# switches.net
KiCad netlist of a schematic drawn in Altium Designer
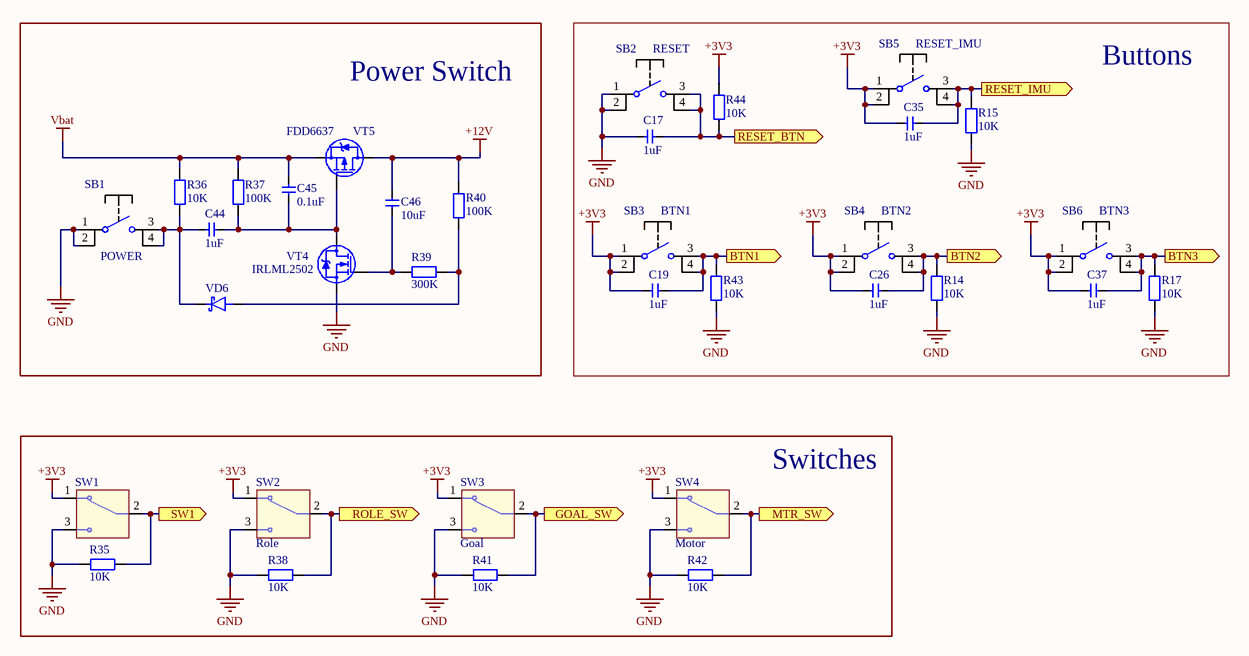
[diagram p0: switches.SchDoc]

(export (version "E")
  (design (tool "Eeschema 10.0.6"))
  (components
    (comp (ref "C17")
      (value "1uF")
      (footprint "CAP0805")
      (description "Ceramic SMD Cap")
      (libsource (lib "Asterisk") (part "CAP Ceramic"))
    )
    (comp (ref "C19")
      (value "1uF")
      (footprint "CAP0805")
      (description "Ceramic SMD Cap")
      (libsource (lib "Asterisk") (part "CAP Ceramic"))
    )
    (comp (ref "C26")
      (value "1uF")
      (footprint "CAP0805")
      (description "Ceramic SMD Cap")
      (libsource (lib "Asterisk") (part "CAP Ceramic"))
    )
    (comp (ref "C35")
      (value "1uF")
      (footprint "CAP0805")
      (description "Ceramic SMD Cap")
      (libsource (lib "Asterisk") (part "CAP Ceramic"))
    )
    (comp (ref "C37")
      (value "1uF")
      (footprint "CAP0805")
      (description "Ceramic SMD Cap")
      (libsource (lib "Asterisk") (part "CAP Ceramic"))
    )
    (comp (ref "C44")
      (value "1uF")
      (footprint "CAP0805")
      (description "Ceramic SMD Cap")
      (libsource (lib "Asterisk") (part "CAP Ceramic"))
    )
    (comp (ref "C45")
      (value "0.1uF")
      (footprint "CAP0805")
      (description "Ceramic SMD Cap")
      (libsource (lib "Asterisk") (part "CAP Ceramic"))
    )
    (comp (ref "C46")
      (value "10uF")
      (footprint "CAP0805")
      (description "Ceramic SMD Cap")
      (libsource (lib "Asterisk") (part "CAP Ceramic"))
    )
    (comp (ref "R14")
      (value "10K")
      (footprint "RES0805")
      (description "RES smd")
      (libsource (lib "Asterisk") (part "RES"))
    )
    (comp (ref "R15")
      (value "10K")
      (footprint "RES0805")
      (description "RES smd")
      (libsource (lib "Asterisk") (part "RES"))
    )
    (comp (ref "R17")
      (value "10K")
      (footprint "RES0805")
      (description "RES smd")
      (libsource (lib "Asterisk") (part "RES"))
    )
    (comp (ref "R35")
      (value "10K")
      (footprint "RES0805")
      (description "RES smd")
      (libsource (lib "Asterisk") (part "RES"))
    )
    (comp (ref "R36")
      (value "10K")
      (footprint "RES0805")
      (description "RES smd")
      (libsource (lib "Asterisk") (part "RES"))
    )
    (comp (ref "R37")
      (value "100K")
      (footprint "RES0805")
      (description "RES smd")
      (libsource (lib "Asterisk") (part "RES"))
    )
    (comp (ref "R38")
      (value "10K")
      (footprint "RES0805")
      (description "RES smd")
      (libsource (lib "Asterisk") (part "RES"))
    )
    (comp (ref "R39")
      (value "300K")
      (footprint "RES0805")
      (description "RES smd")
      (libsource (lib "Asterisk") (part "RES"))
    )
    (comp (ref "R40")
      (value "100K")
      (footprint "RES0805")
      (description "RES smd")
      (libsource (lib "Asterisk") (part "RES"))
    )
    (comp (ref "R41")
      (value "10K")
      (footprint "RES0805")
      (description "RES smd")
      (libsource (lib "Asterisk") (part "RES"))
    )
    (comp (ref "R42")
      (value "10K")
      (footprint "RES0805")
      (description "RES smd")
      (libsource (lib "Asterisk") (part "RES"))
    )
    (comp (ref "R43")
      (value "10K")
      (footprint "RES0805")
      (description "RES smd")
      (libsource (lib "Asterisk") (part "RES"))
    )
    (comp (ref "R44")
      (value "10K")
      (footprint "RES0805")
      (description "RES smd")
      (libsource (lib "Asterisk") (part "RES"))
    )
    (comp (ref "SB1")
      (value "POWER")
      (footprint "DTSM-61N-V-T/R")
      (libsource (lib "Asterisk") (part "Button"))
    )
    (comp (ref "SB2")
      (value "RESET")
      (footprint "DTSM-61N-V-T/R")
      (libsource (lib "Asterisk") (part "Button"))
    )
    (comp (ref "SB3")
      (value "BTN1")
      (footprint "DTSM-61N-V-T/R")
      (libsource (lib "Asterisk") (part "Button"))
    )
    (comp (ref "SB4")
      (value "BTN2")
      (footprint "DTSM-61N-V-T/R")
      (libsource (lib "Asterisk") (part "Button"))
    )
    (comp (ref "SB5")
      (value "RESET_IMU")
      (footprint "DTSM-61N-V-T/R")
      (libsource (lib "Asterisk") (part "Button"))
    )
    (comp (ref "SB6")
      (value "BTN3")
      (footprint "DTSM-61N-V-T/R")
      (libsource (lib "Asterisk") (part "Button"))
    )
    (comp (ref "SW1")
      (value "ESP1010")
      (footprint "ESP1010")
      (description "2 pos switch")
      (libsource (lib "Asterisk") (part "ESP1010"))
    )
    (comp (ref "SW2")
      (value "Role")
      (footprint "ESP1010")
      (description "2 pos switch")
      (libsource (lib "Asterisk") (part "ESP1010"))
    )
    (comp (ref "SW3")
      (value "Goal")
      (footprint "ESP1010")
      (description "2 pos switch")
      (libsource (lib "Asterisk") (part "ESP1010"))
    )
    (comp (ref "SW4")
      (value "Motor")
      (footprint "ESP1010")
      (description "2 pos switch")
      (libsource (lib "Asterisk") (part "ESP1010"))
    )
    (comp (ref "VD6")
      (value "Diode Schottky")
      (footprint "DO-214AC (SMA)")
      (libsource (lib "Asterisk") (part "Diode Schottky"))
    )
    (comp (ref "VT4")
      (value "IRLML2502")
      (footprint "SOT-23-3")
      (description "N-MOSFET\r\nUds = 20 V\r\nIds = 4.2 A\r\nRds = 0.035 Ohm\r\nP = 8 W")
      (libsource (lib "Asterisk") (part "IRLML2502"))
    )
    (comp (ref "VT5")
      (value "FDD6637")
      (footprint "DPAK")
      (description "P-MOSFET\r\nUds = 40 V\r\nIds = 40 A\r\nRds = 0.012 Ohm\r\nP = 3.0 W")
      (libsource (lib "Asterisk") (part "FDD6637"))
    )
  )
  (nets
    (net (code "1") (name "+3V3") (class "Default")
      (node (ref "C19") (pin "1") (pinfunction "1_1") (pintype "passive"))
      (node (ref "C26") (pin "1") (pinfunction "1_1") (pintype "passive"))
      (node (ref "C35") (pin "1") (pinfunction "1_1") (pintype "passive"))
      (node (ref "C37") (pin "1") (pinfunction "1_1") (pintype "passive"))
      (node (ref "R44") (pin "2") (pinfunction "2_2") (pintype "passive"))
      (node (ref "SB3") (pin "1") (pinfunction "1_1") (pintype "passive"))
      (node (ref "SB3") (pin "2") (pinfunction "2_2") (pintype "passive"))
      (node (ref "SB4") (pin "1") (pinfunction "1_1") (pintype "passive"))
      (node (ref "SB4") (pin "2") (pinfunction "2_2") (pintype "passive"))
      (node (ref "SB5") (pin "1") (pinfunction "1_1") (pintype "passive"))
      (node (ref "SB5") (pin "2") (pinfunction "2_2") (pintype "passive"))
      (node (ref "SB6") (pin "1") (pinfunction "1_1") (pintype "passive"))
      (node (ref "SB6") (pin "2") (pinfunction "2_2") (pintype "passive"))
      (node (ref "SW1") (pin "1") (pinfunction "1_1") (pintype "passive"))
      (node (ref "SW2") (pin "1") (pinfunction "1_1") (pintype "passive"))
      (node (ref "SW3") (pin "1") (pinfunction "1_1") (pintype "passive"))
      (node (ref "SW4") (pin "1") (pinfunction "1_1") (pintype "passive"))
    )
    (net (code "2") (name "+12V") (class "Default")
      (node (ref "C46") (pin "2") (pinfunction "2_2") (pintype "passive"))
      (node (ref "R40") (pin "2") (pinfunction "2_2") (pintype "passive"))
      (node (ref "VT5") (pin "D") (pinfunction "D_D") (pintype "passive"))
    )
    (net (code "3") (name "/BTN1") (class "Default")
      (node (ref "C19") (pin "2") (pinfunction "2_2") (pintype "passive"))
      (node (ref "R43") (pin "2") (pinfunction "2_2") (pintype "passive"))
      (node (ref "SB3") (pin "3") (pinfunction "3_3") (pintype "passive"))
      (node (ref "SB3") (pin "4") (pinfunction "4_4") (pintype "passive"))
    )
    (net (code "4") (name "/BTN2") (class "Default")
      (node (ref "C26") (pin "2") (pinfunction "2_2") (pintype "passive"))
      (node (ref "R14") (pin "2") (pinfunction "2_2") (pintype "passive"))
      (node (ref "SB4") (pin "3") (pinfunction "3_3") (pintype "passive"))
      (node (ref "SB4") (pin "4") (pinfunction "4_4") (pintype "passive"))
    )
    (net (code "5") (name "/BTN3") (class "Default")
      (node (ref "C37") (pin "2") (pinfunction "2_2") (pintype "passive"))
      (node (ref "R17") (pin "2") (pinfunction "2_2") (pintype "passive"))
      (node (ref "SB6") (pin "3") (pinfunction "3_3") (pintype "passive"))
      (node (ref "SB6") (pin "4") (pinfunction "4_4") (pintype "passive"))
    )
    (net (code "6") (name "/GOAL_SW") (class "Default")
      (node (ref "R41") (pin "2") (pinfunction "2_2") (pintype "passive"))
      (node (ref "SW3") (pin "2") (pinfunction "2_2") (pintype "passive"))
    )
    (net (code "7") (name "/MTR_SW") (class "Default")
      (node (ref "R42") (pin "2") (pinfunction "2_2") (pintype "passive"))
      (node (ref "SW4") (pin "2") (pinfunction "2_2") (pintype "passive"))
    )
    (net (code "8") (name "/RESET_BTN") (class "Default")
      (node (ref "C17") (pin "2") (pinfunction "2_2") (pintype "passive"))
      (node (ref "R44") (pin "1") (pinfunction "1_1") (pintype "passive"))
      (node (ref "SB2") (pin "3") (pinfunction "3_3") (pintype "passive"))
      (node (ref "SB2") (pin "4") (pinfunction "4_4") (pintype "passive"))
    )
    (net (code "9") (name "/RESET_IMU") (class "Default")
      (node (ref "C35") (pin "2") (pinfunction "2_2") (pintype "passive"))
      (node (ref "R15") (pin "2") (pinfunction "2_2") (pintype "passive"))
      (node (ref "SB5") (pin "3") (pinfunction "3_3") (pintype "passive"))
      (node (ref "SB5") (pin "4") (pinfunction "4_4") (pintype "passive"))
    )
    (net (code "10") (name "/ROLE_SW") (class "Default")
      (node (ref "R38") (pin "2") (pinfunction "2_2") (pintype "passive"))
      (node (ref "SW2") (pin "2") (pinfunction "2_2") (pintype "passive"))
    )
    (net (code "11") (name "/SW1") (class "Default")
      (node (ref "R35") (pin "2") (pinfunction "2_2") (pintype "passive"))
      (node (ref "SW1") (pin "2") (pinfunction "2_2") (pintype "passive"))
    )
    (net (code "12") (name "GND") (class "Default")
      (node (ref "C17") (pin "1") (pinfunction "1_1") (pintype "passive"))
      (node (ref "R14") (pin "1") (pinfunction "1_1") (pintype "passive"))
      (node (ref "R15") (pin "1") (pinfunction "1_1") (pintype "passive"))
      (node (ref "R17") (pin "1") (pinfunction "1_1") (pintype "passive"))
      (node (ref "R35") (pin "1") (pinfunction "1_1") (pintype "passive"))
      (node (ref "R38") (pin "1") (pinfunction "1_1") (pintype "passive"))
      (node (ref "R41") (pin "1") (pinfunction "1_1") (pintype "passive"))
      (node (ref "R42") (pin "1") (pinfunction "1_1") (pintype "passive"))
      (node (ref "R43") (pin "1") (pinfunction "1_1") (pintype "passive"))
      (node (ref "SB1") (pin "1") (pinfunction "1_1") (pintype "passive"))
      (node (ref "SB1") (pin "2") (pinfunction "2_2") (pintype "passive"))
      (node (ref "SB2") (pin "1") (pinfunction "1_1") (pintype "passive"))
      (node (ref "SB2") (pin "2") (pinfunction "2_2") (pintype "passive"))
      (node (ref "SW1") (pin "3") (pinfunction "3_3") (pintype "passive"))
      (node (ref "SW2") (pin "3") (pinfunction "3_3") (pintype "passive"))
      (node (ref "SW3") (pin "3") (pinfunction "3_3") (pintype "passive"))
      (node (ref "SW4") (pin "3") (pinfunction "3_3") (pintype "passive"))
      (node (ref "VT4") (pin "S") (pinfunction "S_S") (pintype "passive"))
    )
    (net (code "13") (name "Net-(C44-Pad1)") (class "Default")
      (node (ref "C44") (pin "1") (pinfunction "1_1") (pintype "passive"))
      (node (ref "C45") (pin "1") (pinfunction "1_1") (pintype "passive"))
      (node (ref "R37") (pin "2") (pinfunction "2_2") (pintype "passive"))
      (node (ref "VT4") (pin "D") (pinfunction "D_D") (pintype "passive"))
      (node (ref "VT5") (pin "G") (pinfunction "G_G") (pintype "passive"))
    )
    (net (code "14") (name "Net-(C44-Pad2)") (class "Default")
      (node (ref "C44") (pin "2") (pinfunction "2_2") (pintype "passive"))
      (node (ref "R36") (pin "2") (pinfunction "2_2") (pintype "passive"))
      (node (ref "SB1") (pin "3") (pinfunction "3_3") (pintype "passive"))
      (node (ref "SB1") (pin "4") (pinfunction "4_4") (pintype "passive"))
      (node (ref "VD6") (pin "K") (pinfunction "K_K") (pintype "passive"))
    )
    (net (code "15") (name "Net-(C46-Pad1)") (class "Default")
      (node (ref "C46") (pin "1") (pinfunction "1_1") (pintype "passive"))
      (node (ref "R39") (pin "2") (pinfunction "2_2") (pintype "passive"))
      (node (ref "VT4") (pin "G") (pinfunction "G_G") (pintype "passive"))
    )
    (net (code "16") (name "Net-(R39-Pad1)") (class "Default")
      (node (ref "R39") (pin "1") (pinfunction "1_1") (pintype "passive"))
      (node (ref "R40") (pin "1") (pinfunction "1_1") (pintype "passive"))
      (node (ref "VD6") (pin "A") (pinfunction "A_A") (pintype "passive"))
    )
    (net (code "17") (name "Vbat") (class "Default")
      (node (ref "C45") (pin "2") (pinfunction "2_2") (pintype "passive"))
      (node (ref "R36") (pin "1") (pinfunction "1_1") (pintype "passive"))
      (node (ref "R37") (pin "1") (pinfunction "1_1") (pintype "passive"))
      (node (ref "VT5") (pin "S") (pinfunction "S_S") (pintype "passive"))
    )
  )
)
